# Quadruped.net
KiCad netlist of a schematic drawn in Altium Designer
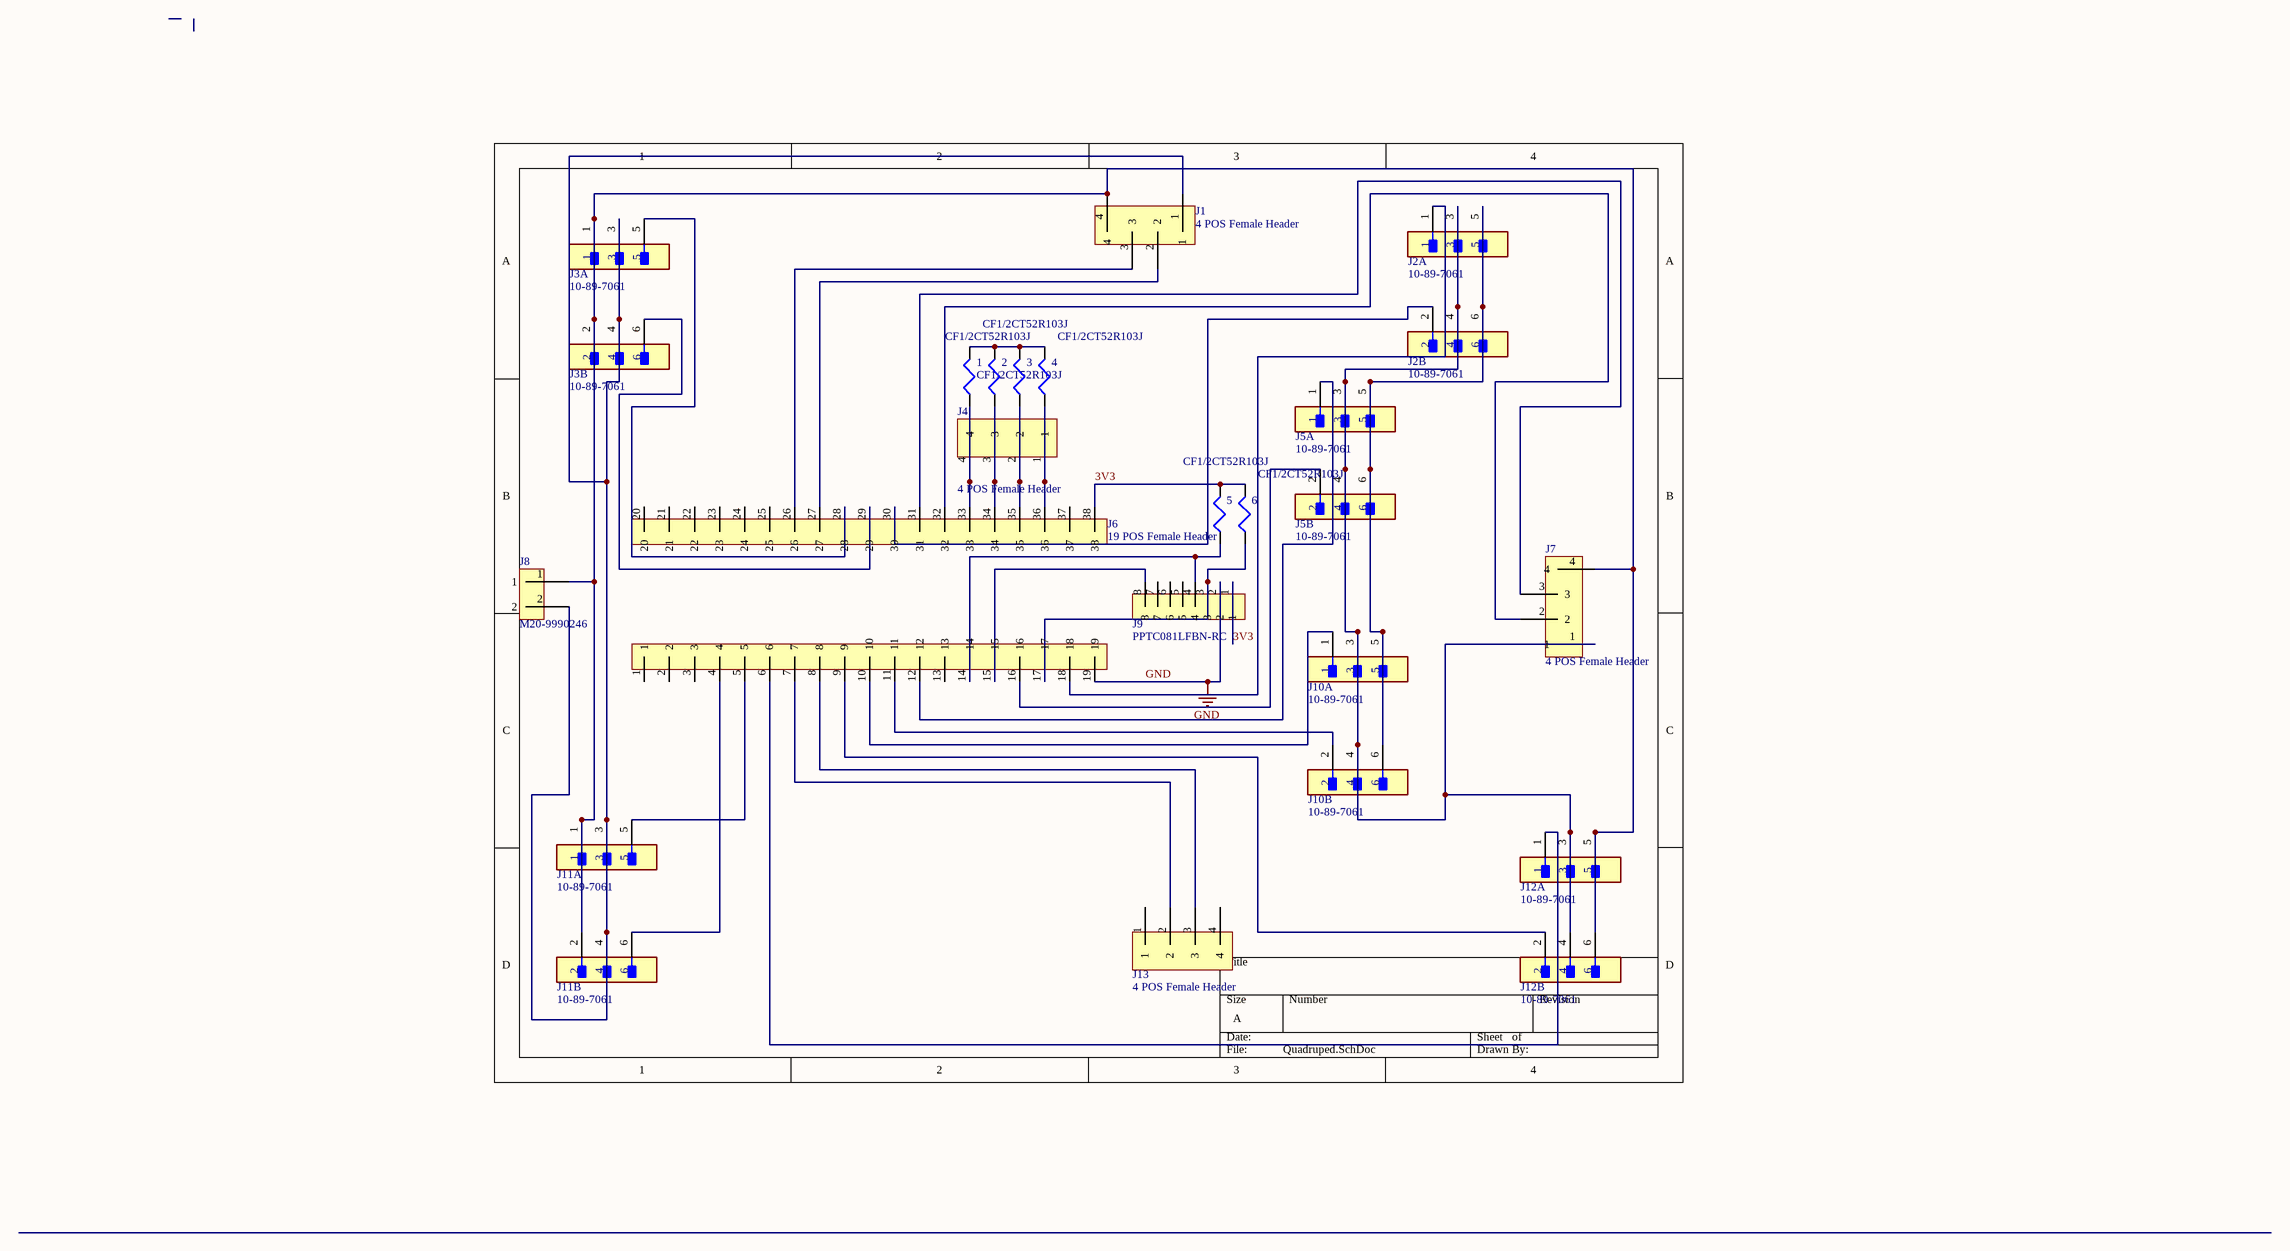
[diagram p0: Quadruped.SchDoc]

(export (version "E")
  (design (tool "Eeschema 10.0.6"))
  (components
    (comp (ref "1")
      (value "CF1/2CT52R103J")
      (footprint "10K 1/2W")
      (description "Res, 10K, 0.5W, Axial, Carbon Film Rohs Compliant: Yes ¦Koa CF1/2CT52R103J")
      (fields (field (name "MANUFACTURER") "KOA Speer") (field (name "TOLERANCE") "5%"))
      (libsource (lib "Try1") (part "CF1/2CT52R103J"))
    )
    (comp (ref "2")
      (value "CF1/2CT52R103J")
      (footprint "10K 1/2W")
      (description "Res, 10K, 0.5W, Axial, Carbon Film Rohs Compliant: Yes ¦Koa CF1/2CT52R103J")
      (fields (field (name "MANUFACTURER") "KOA Speer") (field (name "TOLERANCE") "5%"))
      (libsource (lib "Try1") (part "CF1/2CT52R103J"))
    )
    (comp (ref "3")
      (value "CF1/2CT52R103J")
      (footprint "10K 1/2W")
      (description "Res, 10K, 0.5W, Axial, Carbon Film Rohs Compliant: Yes ¦Koa CF1/2CT52R103J")
      (fields (field (name "MANUFACTURER") "KOA Speer") (field (name "TOLERANCE") "5%"))
      (libsource (lib "Try1") (part "CF1/2CT52R103J"))
    )
    (comp (ref "4")
      (value "CF1/2CT52R103J")
      (footprint "10K 1/2W")
      (description "Res, 10K, 0.5W, Axial, Carbon Film Rohs Compliant: Yes ¦Koa CF1/2CT52R103J")
      (fields (field (name "MANUFACTURER") "KOA Speer") (field (name "TOLERANCE") "5%"))
      (libsource (lib "Try1") (part "CF1/2CT52R103J"))
    )
    (comp (ref "5")
      (value "CF1/2CT52R103J")
      (footprint "10K 1/2W")
      (description "Res, 10K, 0.5W, Axial, Carbon Film Rohs Compliant: Yes ¦Koa CF1/2CT52R103J")
      (fields (field (name "MANUFACTURER") "KOA Speer") (field (name "TOLERANCE") "5%"))
      (libsource (lib "Try1") (part "CF1/2CT52R103J"))
    )
    (comp (ref "6")
      (value "CF1/2CT52R103J")
      (footprint "10K 1/2W")
      (description "Res, 10K, 0.5W, Axial, Carbon Film Rohs Compliant: Yes ¦Koa CF1/2CT52R103J")
      (fields (field (name "MANUFACTURER") "KOA Speer") (field (name "TOLERANCE") "5%"))
      (libsource (lib "Try1") (part "CF1/2CT52R103J"))
    )
    (comp (ref "J1")
      (value "4 POS Female Header")
      (footprint "SULLINS_PPTC041LFBN-RC")
      (description "CONN HDR 4POS 0.1 GOLD PCB")
      (fields
        (field (name "MANUFACTURER") "Sullins")
        (field (name "MANUFACTURER PART NUMBER") "PPPC041LFBN-RC")
      )
      (libsource (lib "") (part "PPPC041LFBN-RC_OPPOSITE_1"))
    )
    (comp (ref "J2")
      (value "10-89-7061")
      (footprint "3x2_MALE_HEADER")
      (description "CONN HEADER VERT 6POS 2.54MM")
      (libsource (lib "Try1") (part "2654a11fb13586ecb194516b1c997bc"))
    )
    (comp (ref "J3")
      (value "10-89-7061")
      (footprint "3x2_MALE_HEADER")
      (description "CONN HEADER VERT 6POS 2.54MM")
      (libsource (lib "Try1") (part "2654a11fb13586ecb194516b1c997bc"))
    )
    (comp (ref "J4")
      (value "4 POS Female Header")
      (footprint "SULLINS_PPTC041LFBN-RC")
      (description "CONN HDR 4POS 0.1 GOLD PCB")
      (fields
        (field (name "MANUFACTURER") "Sullins")
        (field (name "MANUFACTURER PART NUMBER") "PPPC041LFBN-RC")
      )
      (libsource (lib "") (part "PPPC041LFBN-RC_1"))
    )
    (comp (ref "J5")
      (value "10-89-7061")
      (footprint "3x2_MALE_HEADER")
      (description "CONN HEADER VERT 6POS 2.54MM")
      (libsource (lib "Try1") (part "2654a11fb13586ecb194516b1c997bc"))
    )
    (comp (ref "J6")
      (value "19 POS Female Header")
      (footprint "ESP_32")
      (description "CONN HDR 19POS 0.1 TIN PCB")
      (fields
        (field (name "MANUFACTURER") "Sullins")
        (field (name "MANUFACTURER PART NUMBER") "PPTC191LFBN-RC")
      )
      (libsource (lib "Try1") (part "PPTC191LFBN-RC"))
    )
    (comp (ref "J7")
      (value "4 POS Female Header")
      (footprint "SULLINS_PPTC041LFBN-RC")
      (description "CONN HDR 4POS 0.1 GOLD PCB")
      (fields
        (field (name "MANUFACTURER") "Sullins")
        (field (name "MANUFACTURER PART NUMBER") "PPPC041LFBN-RC")
      )
      (libsource (lib "Try1") (part "PPPC041LFBN-RC_OPPOSITE"))
    )
    (comp (ref "J8")
      (value "M20-9990246")
      (footprint "2x1_MALE_HEADER")
      (description "2.54mm (0.1\") Pitch SIL Vertical PC Tail Pin Header, 6.1mm mating pin height, tin, 2 contacts")
      (fields (field (name "MANUFACTURER") "Harwin"))
      (libsource (lib "Try1") (part "M20-9990246"))
    )
    (comp (ref "J9")
      (value "PPTC081LFBN-RC")
      (footprint "8POS_FEMALE_HEADER")
      (description "Female, 8C, Straight, .100\"CC; 3.20mm Tail, No Mt. 100u\" Tin; PBT, Phos Bronze, 105 C")
      (fields (field (name "MANUFACTURER") "Sullins"))
      (libsource (lib "Try1") (part "PPTC081LFBN-RC"))
    )
    (comp (ref "J10")
      (value "10-89-7061")
      (footprint "3x2_MALE_HEADER")
      (description "CONN HEADER VERT 6POS 2.54MM")
      (libsource (lib "Try1") (part "2654a11fb13586ecb194516b1c997bc"))
    )
    (comp (ref "J11")
      (value "10-89-7061")
      (footprint "3x2_MALE_HEADER")
      (description "CONN HEADER VERT 6POS 2.54MM")
      (libsource (lib "Try1") (part "2654a11fb13586ecb194516b1c997bc"))
    )
    (comp (ref "J12")
      (value "10-89-7061")
      (footprint "3x2_MALE_HEADER")
      (description "CONN HEADER VERT 6POS 2.54MM")
      (libsource (lib "Try1") (part "2654a11fb13586ecb194516b1c997bc"))
    )
    (comp (ref "J13")
      (value "4 POS Female Header")
      (footprint "SULLINS_PPTC041LFBN-RC")
      (description "CONN HDR 4POS 0.1 GOLD PCB")
      (fields
        (field (name "MANUFACTURER") "Sullins")
        (field (name "MANUFACTURER PART NUMBER") "PPPC041LFBN-RC")
      )
      (libsource (lib "Try1") (part "PPPC041LFBN-RC"))
    )
  )
  (nets
    (net (code "1") (name "/3V3") (class "Default")
      (node (ref "5") (pin "2") (pinfunction "2_2") (pintype "passive"))
      (node (ref "6") (pin "2") (pinfunction "2_2") (pintype "passive"))
      (node (ref "J6") (pin "38") (pinfunction "38_38") (pintype "passive"))
      (node (ref "J9") (pin "1") (pinfunction "1_1") (pintype "passive"))
    )
    (net (code "2") (name "GND") (class "Default")
      (node (ref "J6") (pin "19") (pinfunction "19_19") (pintype "passive"))
      (node (ref "J9") (pin "2") (pinfunction "2_2") (pintype "passive"))
    )
    (net (code "3") (name "Net-(1-Pad1)") (class "Default")
      (node (ref "1") (pin "1") (pinfunction "1_1") (pintype "passive"))
      (node (ref "J4") (pin "4") (pinfunction "4_4") (pintype "passive"))
      (node (ref "J6") (pin "33") (pinfunction "33_33") (pintype "passive"))
    )
    (net (code "4") (name "Net-(1-Pad2)") (class "Default")
      (node (ref "1") (pin "2") (pinfunction "2_2") (pintype "passive"))
      (node (ref "2") (pin "2") (pinfunction "2_2") (pintype "passive"))
      (node (ref "3") (pin "2") (pinfunction "2_2") (pintype "passive"))
      (node (ref "4") (pin "2") (pinfunction "2_2") (pintype "passive"))
    )
    (net (code "5") (name "Net-(2-Pad1)") (class "Default")
      (node (ref "2") (pin "1") (pinfunction "1_1") (pintype "passive"))
      (node (ref "J4") (pin "3") (pinfunction "3_3") (pintype "passive"))
      (node (ref "J6") (pin "34") (pinfunction "34_34") (pintype "passive"))
    )
    (net (code "6") (name "Net-(3-Pad1)") (class "Default")
      (node (ref "3") (pin "1") (pinfunction "1_1") (pintype "passive"))
      (node (ref "J4") (pin "2") (pinfunction "2_2") (pintype "passive"))
      (node (ref "J6") (pin "35") (pinfunction "35_35") (pintype "passive"))
    )
    (net (code "7") (name "Net-(4-Pad1)") (class "Default")
      (node (ref "4") (pin "1") (pinfunction "1_1") (pintype "passive"))
      (node (ref "J4") (pin "1") (pinfunction "1_1") (pintype "passive"))
      (node (ref "J6") (pin "36") (pinfunction "36_36") (pintype "passive"))
    )
    (net (code "8") (name "Net-(5-Pad1)") (class "Default")
      (node (ref "5") (pin "1") (pinfunction "1_1") (pintype "passive"))
      (node (ref "J6") (pin "14") (pinfunction "14_14") (pintype "passive"))
      (node (ref "J9") (pin "4") (pinfunction "4_4") (pintype "passive"))
    )
    (net (code "9") (name "Net-(6-Pad1)") (class "Default")
      (node (ref "6") (pin "1") (pinfunction "1_1") (pintype "passive"))
      (node (ref "J6") (pin "17") (pinfunction "17_17") (pintype "passive"))
      (node (ref "J9") (pin "3") (pinfunction "3_3") (pintype "passive"))
    )
    (net (code "10") (name "Net-(J1-Pad1)") (class "Default")
      (node (ref "J1") (pin "1") (pinfunction "1_1") (pintype "passive"))
      (node (ref "J11") (pin "3") (pinfunction "3_3") (pintype "passive"))
      (node (ref "J11") (pin "4") (pinfunction "4_4") (pintype "passive"))
      (node (ref "J3") (pin "3") (pinfunction "3_3") (pintype "passive"))
      (node (ref "J3") (pin "4") (pinfunction "4_4") (pintype "passive"))
      (node (ref "J8") (pin "2") (pinfunction "2_2") (pintype "passive"))
    )
    (net (code "11") (name "Net-(J1-Pad2)") (class "Default")
      (node (ref "J1") (pin "2") (pinfunction "2_2") (pintype "passive"))
      (node (ref "J6") (pin "27") (pinfunction "27_27") (pintype "passive"))
    )
    (net (code "12") (name "Net-(J1-Pad3)") (class "Default")
      (node (ref "J1") (pin "3") (pinfunction "3_3") (pintype "passive"))
      (node (ref "J6") (pin "26") (pinfunction "26_26") (pintype "passive"))
    )
    (net (code "13") (name "Net-(J1-Pad4)") (class "Default")
      (node (ref "J1") (pin "4") (pinfunction "4_4") (pintype "passive"))
      (node (ref "J11") (pin "1") (pinfunction "1_1") (pintype "passive"))
      (node (ref "J11") (pin "2") (pinfunction "2_2") (pintype "passive"))
      (node (ref "J12") (pin "5") (pinfunction "5_5") (pintype "passive"))
      (node (ref "J12") (pin "6") (pinfunction "6_6") (pintype "passive"))
      (node (ref "J3") (pin "1") (pinfunction "1_1") (pintype "passive"))
      (node (ref "J3") (pin "2") (pinfunction "2_2") (pintype "passive"))
      (node (ref "J7") (pin "4") (pinfunction "4_4") (pintype "passive"))
      (node (ref "J8") (pin "1") (pinfunction "1_1") (pintype "passive"))
    )
    (net (code "14") (name "Net-(J2-Pad1)") (class "Default")
      (node (ref "J2") (pin "1") (pinfunction "1_1") (pintype "passive"))
      (node (ref "J6") (pin "18") (pinfunction "18_18") (pintype "passive"))
    )
    (net (code "15") (name "Net-(J2-Pad2)") (class "Default")
      (node (ref "J2") (pin "2") (pinfunction "2_2") (pintype "passive"))
      (node (ref "J6") (pin "30") (pinfunction "30_30") (pintype "passive"))
    )
    (net (code "16") (name "Net-(J3-Pad5)") (class "Default")
      (node (ref "J3") (pin "5") (pinfunction "5_5") (pintype "passive"))
      (node (ref "J6") (pin "28") (pinfunction "28_28") (pintype "passive"))
    )
    (net (code "17") (name "Net-(J3-Pad6)") (class "Default")
      (node (ref "J3") (pin "6") (pinfunction "6_6") (pintype "passive"))
      (node (ref "J6") (pin "29") (pinfunction "29_29") (pintype "passive"))
    )
    (net (code "18") (name "Net-(J5-Pad1)") (class "Default")
      (node (ref "J5") (pin "1") (pinfunction "1_1") (pintype "passive"))
      (node (ref "J6") (pin "12") (pinfunction "12_12") (pintype "passive"))
    )
    (net (code "19") (name "Net-(J5-Pad2)") (class "Default")
      (node (ref "J5") (pin "2") (pinfunction "2_2") (pintype "passive"))
      (node (ref "J6") (pin "16") (pinfunction "16_16") (pintype "passive"))
    )
    (net (code "20") (name "Net-(J6-Pad15)") (class "Default")
      (node (ref "J6") (pin "15") (pinfunction "15_15") (pintype "passive"))
      (node (ref "J9") (pin "8") (pinfunction "8_8") (pintype "passive"))
    )
    (net (code "21") (name "Net-(J6-Pad31)") (class "Default")
      (node (ref "J6") (pin "31") (pinfunction "31_31") (pintype "passive"))
      (node (ref "J7") (pin "3") (pinfunction "3_3") (pintype "passive"))
    )
    (net (code "22") (name "Net-(J6-Pad32)") (class "Default")
      (node (ref "J6") (pin "32") (pinfunction "32_32") (pintype "passive"))
      (node (ref "J7") (pin "2") (pinfunction "2_2") (pintype "passive"))
    )
    (net (code "23") (name "Net-(J10-Pad1)") (class "Default")
      (node (ref "J10") (pin "1") (pinfunction "1_1") (pintype "passive"))
      (node (ref "J6") (pin "10") (pinfunction "10_10") (pintype "passive"))
    )
    (net (code "24") (name "Net-(J10-Pad2)") (class "Default")
      (node (ref "J10") (pin "2") (pinfunction "2_2") (pintype "passive"))
      (node (ref "J6") (pin "11") (pinfunction "11_11") (pintype "passive"))
    )
    (net (code "25") (name "Net-(J10-Pad3)") (class "Default")
      (node (ref "J10") (pin "3") (pinfunction "3_3") (pintype "passive"))
      (node (ref "J10") (pin "4") (pinfunction "4_4") (pintype "passive"))
      (node (ref "J12") (pin "3") (pinfunction "3_3") (pintype "passive"))
      (node (ref "J12") (pin "4") (pinfunction "4_4") (pintype "passive"))
      (node (ref "J2") (pin "3") (pinfunction "3_3") (pintype "passive"))
      (node (ref "J2") (pin "4") (pinfunction "4_4") (pintype "passive"))
      (node (ref "J5") (pin "3") (pinfunction "3_3") (pintype "passive"))
      (node (ref "J5") (pin "4") (pinfunction "4_4") (pintype "passive"))
      (node (ref "J7") (pin "1") (pinfunction "1_1") (pintype "passive"))
    )
    (net (code "26") (name "Net-(J10-Pad5)") (class "Default")
      (node (ref "J10") (pin "5") (pinfunction "5_5") (pintype "passive"))
      (node (ref "J10") (pin "6") (pinfunction "6_6") (pintype "passive"))
      (node (ref "J2") (pin "5") (pinfunction "5_5") (pintype "passive"))
      (node (ref "J2") (pin "6") (pinfunction "6_6") (pintype "passive"))
      (node (ref "J5") (pin "5") (pinfunction "5_5") (pintype "passive"))
      (node (ref "J5") (pin "6") (pinfunction "6_6") (pintype "passive"))
    )
    (net (code "27") (name "Net-(J11-Pad5)") (class "Default")
      (node (ref "J11") (pin "5") (pinfunction "5_5") (pintype "passive"))
      (node (ref "J6") (pin "5") (pinfunction "5_5") (pintype "passive"))
    )
    (net (code "28") (name "Net-(J11-Pad6)") (class "Default")
      (node (ref "J11") (pin "6") (pinfunction "6_6") (pintype "passive"))
      (node (ref "J6") (pin "4") (pinfunction "4_4") (pintype "passive"))
    )
    (net (code "29") (name "Net-(J12-Pad1)") (class "Default")
      (node (ref "J12") (pin "1") (pinfunction "1_1") (pintype "passive"))
      (node (ref "J6") (pin "6") (pinfunction "6_6") (pintype "passive"))
    )
    (net (code "30") (name "Net-(J12-Pad2)") (class "Default")
      (node (ref "J12") (pin "2") (pinfunction "2_2") (pintype "passive"))
      (node (ref "J6") (pin "9") (pinfunction "9_9") (pintype "passive"))
    )
    (net (code "31") (name "Net-(J13-Pad2)") (class "Default")
      (node (ref "J13") (pin "2") (pinfunction "2_2") (pintype "passive"))
      (node (ref "J6") (pin "7") (pinfunction "7_7") (pintype "passive"))
    )
    (net (code "32") (name "Net-(J13-Pad3)") (class "Default")
      (node (ref "J13") (pin "3") (pinfunction "3_3") (pintype "passive"))
      (node (ref "J6") (pin "8") (pinfunction "8_8") (pintype "passive"))
    )
    (net (code "33") (name "unconnected-(J6-Pad1)") (class "Default")
      (node (ref "J6") (pin "1") (pinfunction "1_1") (pintype "passive"))
    )
    (net (code "34") (name "unconnected-(J6-Pad2)") (class "Default")
      (node (ref "J6") (pin "2") (pinfunction "2_2") (pintype "passive"))
    )
    (net (code "35") (name "unconnected-(J6-Pad3)") (class "Default")
      (node (ref "J6") (pin "3") (pinfunction "3_3") (pintype "passive"))
    )
    (net (code "36") (name "unconnected-(J6-Pad13)") (class "Default")
      (node (ref "J6") (pin "13") (pinfunction "13_13") (pintype "passive"))
    )
    (net (code "37") (name "unconnected-(J6-Pad20)") (class "Default")
      (node (ref "J6") (pin "20") (pinfunction "20_20") (pintype "passive"))
    )
    (net (code "38") (name "unconnected-(J6-Pad21)") (class "Default")
      (node (ref "J6") (pin "21") (pinfunction "21_21") (pintype "passive"))
    )
    (net (code "39") (name "unconnected-(J6-Pad22)") (class "Default")
      (node (ref "J6") (pin "22") (pinfunction "22_22") (pintype "passive"))
    )
    (net (code "40") (name "unconnected-(J6-Pad23)") (class "Default")
      (node (ref "J6") (pin "23") (pinfunction "23_23") (pintype "passive"))
    )
    (net (code "41") (name "unconnected-(J6-Pad24)") (class "Default")
      (node (ref "J6") (pin "24") (pinfunction "24_24") (pintype "passive"))
    )
    (net (code "42") (name "unconnected-(J6-Pad25)") (class "Default")
      (node (ref "J6") (pin "25") (pinfunction "25_25") (pintype "passive"))
    )
    (net (code "43") (name "unconnected-(J6-Pad37)") (class "Default")
      (node (ref "J6") (pin "37") (pinfunction "37_37") (pintype "passive"))
    )
    (net (code "44") (name "unconnected-(J9-Pad5)") (class "Default")
      (node (ref "J9") (pin "5") (pinfunction "5_5") (pintype "passive"))
    )
    (net (code "45") (name "unconnected-(J9-Pad6)") (class "Default")
      (node (ref "J9") (pin "6") (pinfunction "6_6") (pintype "passive"))
    )
    (net (code "46") (name "unconnected-(J9-Pad7)") (class "Default")
      (node (ref "J9") (pin "7") (pinfunction "7_7") (pintype "passive"))
    )
    (net (code "47") (name "unconnected-(J13-Pad1)") (class "Default")
      (node (ref "J13") (pin "1") (pinfunction "1_1") (pintype "passive"))
    )
    (net (code "48") (name "unconnected-(J13-Pad4)") (class "Default")
      (node (ref "J13") (pin "4") (pinfunction "4_4") (pintype "passive"))
    )
  )
)
